# PCB_3U_Tester.net
KiCad netlist of a schematic drawn in Altium Designer
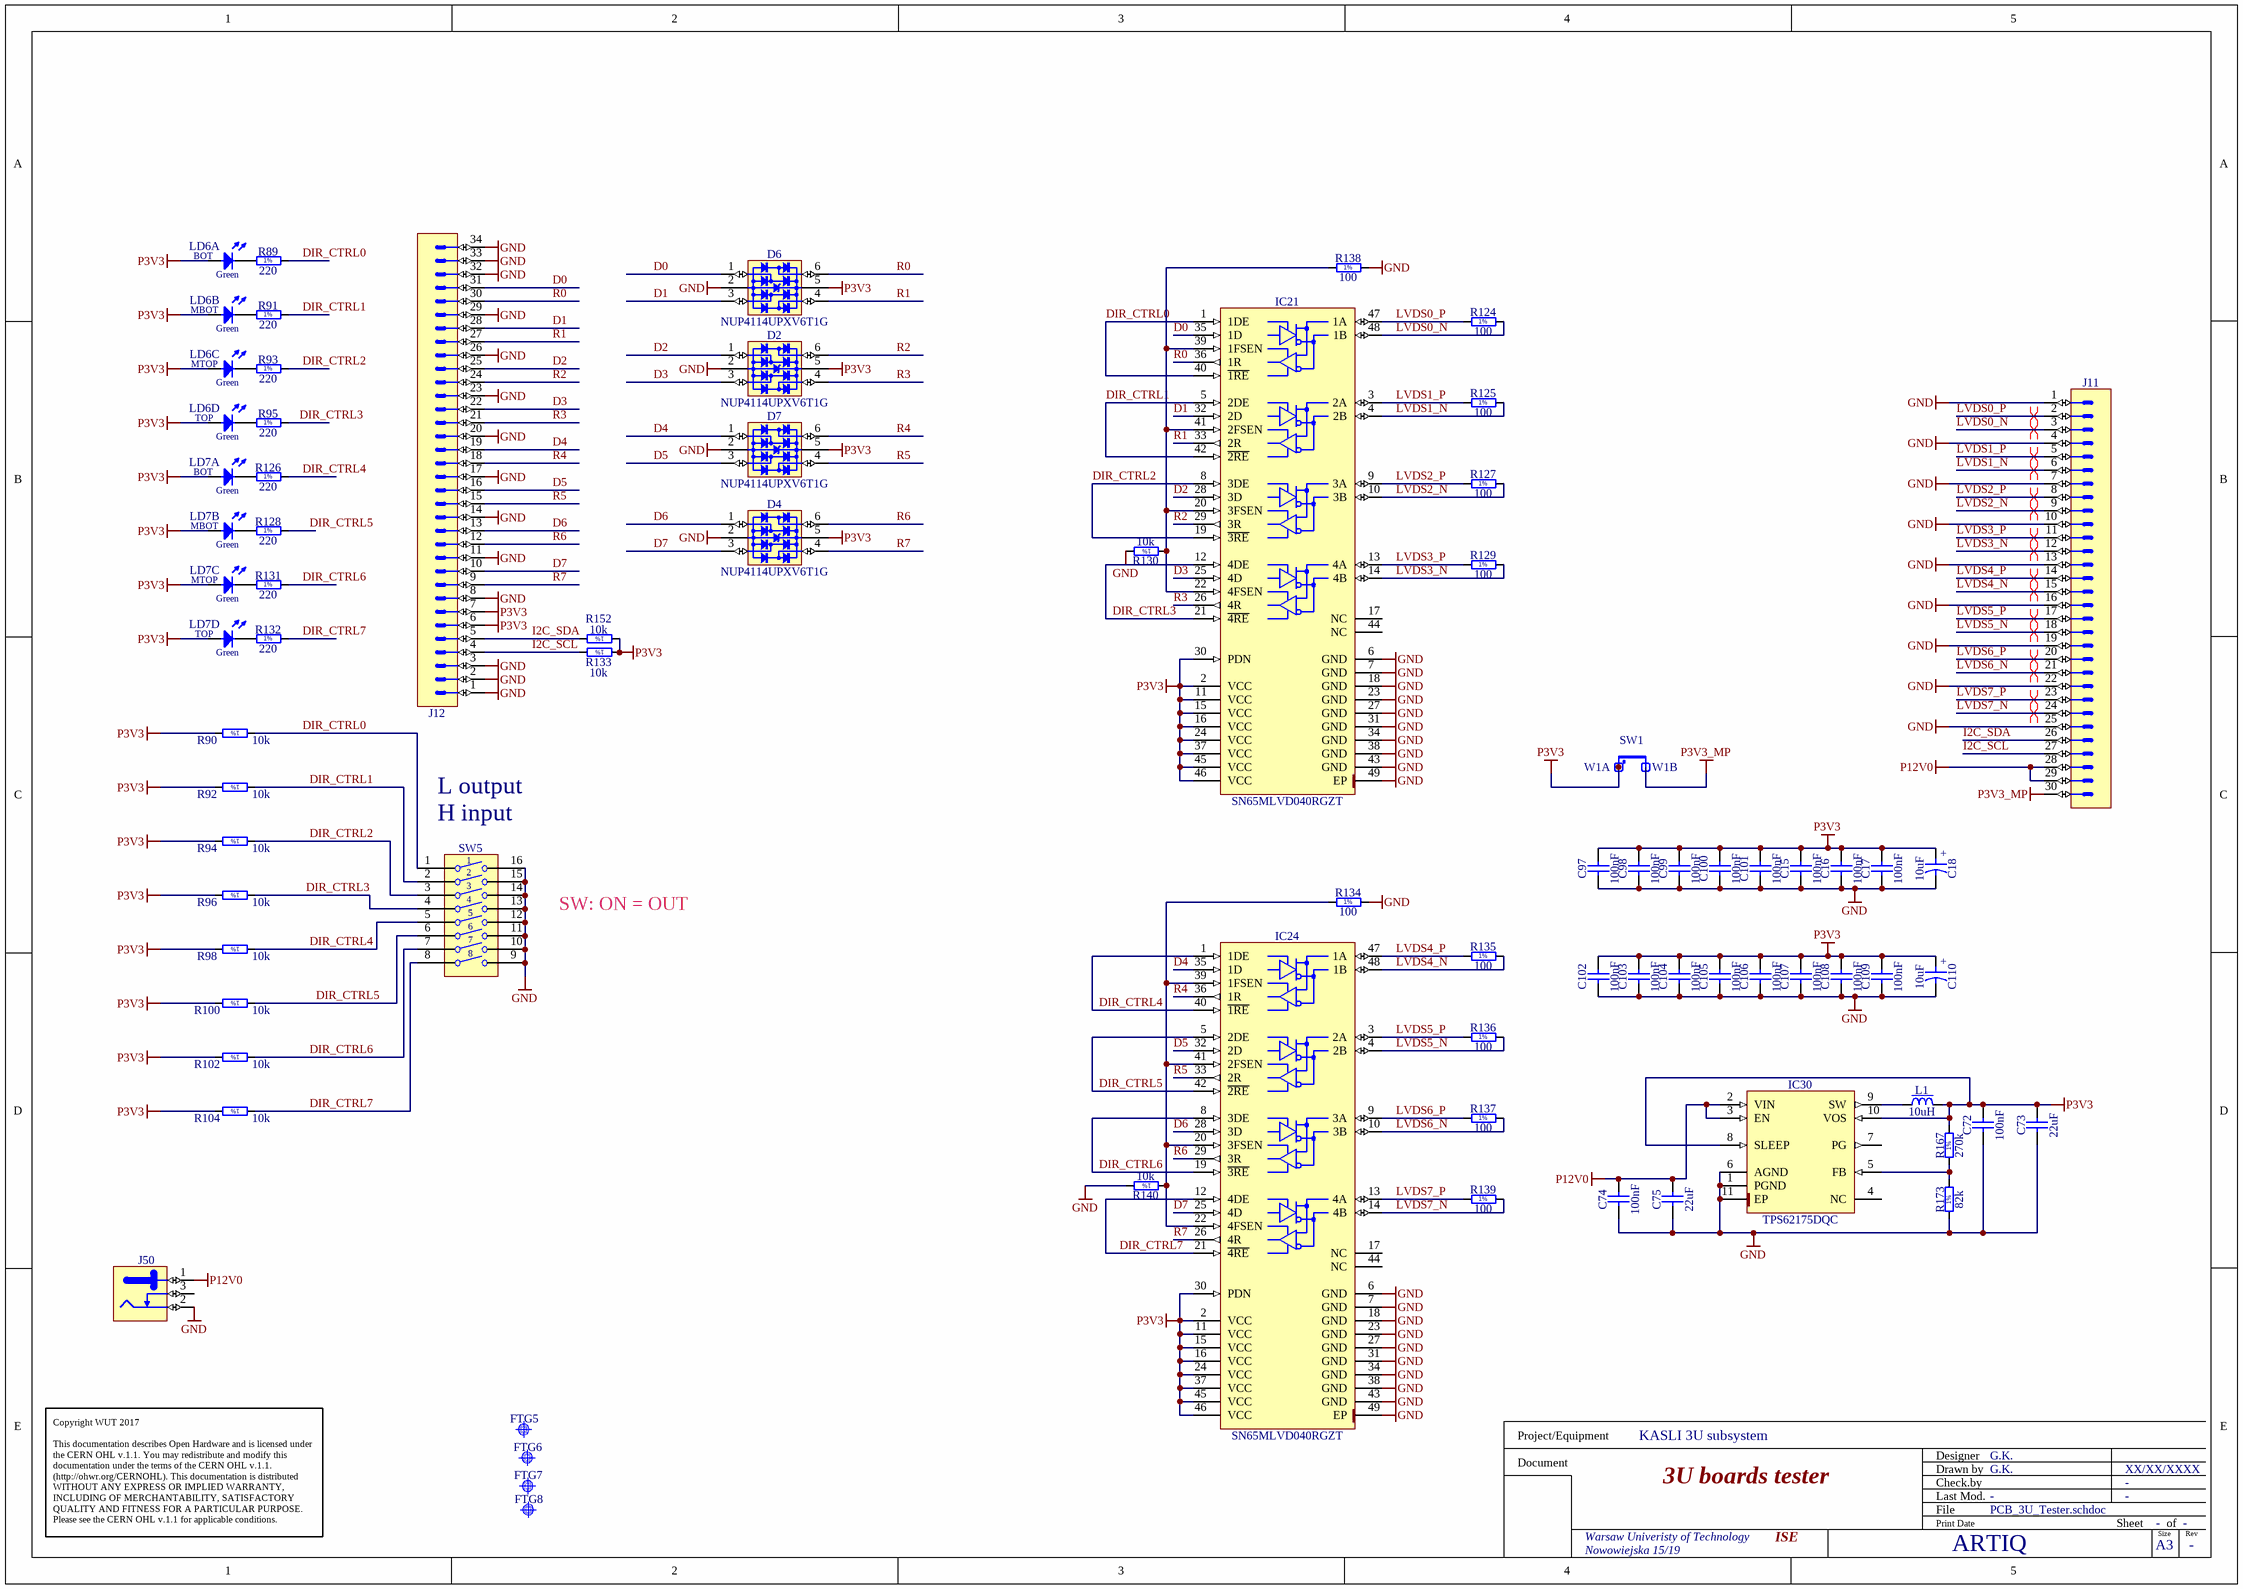
[diagram p0: PCB_3U_Tester.schdoc]

(export (version "E")
  (design (tool "Eeschema 10.0.6"))
  (components
    (comp (ref "C15")
      (value "100nF")
      (footprint "CAPC1005X55N")
      (description "Non-polarised capacitor")
      (fields (field (name "PART NUMBER") "CC0402_100NF_16V_10%_X5R") (field (name "VOLTAGE") "16V"))
      (libsource (lib "Capacitors") (part "Capacitor - non polarized"))
    )
    (comp (ref "C16")
      (value "100nF")
      (footprint "CAPC1005X55N")
      (description "Non-polarised capacitor")
      (fields (field (name "PART NUMBER") "CC0402_100NF_16V_10%_X5R") (field (name "VOLTAGE") "16V"))
      (libsource (lib "Capacitors") (part "Capacitor - non polarized"))
    )
    (comp (ref "C17")
      (value "100nF")
      (footprint "CAPC1005X55N")
      (description "Non-polarised capacitor")
      (fields (field (name "PART NUMBER") "CC0402_100NF_16V_10%_X5R") (field (name "VOLTAGE") "16V"))
      (libsource (lib "Capacitors") (part "Capacitor - non polarized"))
    )
    (comp (ref "C18")
      (value "10uF")
      (footprint "CAPAE430X540N")
      (description "Polarised capacitor")
      (fields (field (name "PART NUMBER") "CAE430-540_10UF_16V_20%") (field (name "VOLTAGE") "16V"))
      (libsource (lib "Capacitors") (part "Capacitor - polarized"))
    )
    (comp (ref "C72")
      (value "100nF")
      (footprint "CAPC1005X55N")
      (description "Non-polarised capacitor")
      (fields (field (name "PART NUMBER") "CC0402_100NF_16V_10%_X5R") (field (name "VOLTAGE") "16V"))
      (libsource (lib "Capacitors") (part "Capacitor - non polarized"))
    )
    (comp (ref "C73")
      (value "22uF")
      (footprint "CAPC2012X135N")
      (description "Non-polarised capacitor")
      (fields (field (name "PART NUMBER") "CC0805_22UF_16V_10%_X5R") (field (name "VOLTAGE") "16V"))
      (libsource (lib "Capacitors") (part "Capacitor - non polarized"))
    )
    (comp (ref "C74")
      (value "100nF")
      (footprint "CAPC1005X55N")
      (description "Non-polarised capacitor")
      (fields (field (name "PART NUMBER") "CC0402_100NF_16V_10%_X5R") (field (name "VOLTAGE") "16V"))
      (libsource (lib "Capacitors") (part "Capacitor - non polarized"))
    )
    (comp (ref "C75")
      (value "22uF")
      (footprint "CAPC2012X135N")
      (description "Non-polarised capacitor")
      (fields (field (name "PART NUMBER") "CC0805_22UF_16V_10%_X5R") (field (name "VOLTAGE") "16V"))
      (libsource (lib "Capacitors") (part "Capacitor - non polarized"))
    )
    (comp (ref "C97")
      (value "100nF")
      (footprint "CAPC1005X55N")
      (description "Non-polarised capacitor")
      (fields (field (name "PART NUMBER") "CC0402_100NF_16V_10%_X5R") (field (name "VOLTAGE") "16V"))
      (libsource (lib "Capacitors") (part "Capacitor - non polarized"))
    )
    (comp (ref "C98")
      (value "100nF")
      (footprint "CAPC1005X55N")
      (description "Non-polarised capacitor")
      (fields (field (name "PART NUMBER") "CC0402_100NF_16V_10%_X5R") (field (name "VOLTAGE") "16V"))
      (libsource (lib "Capacitors") (part "Capacitor - non polarized"))
    )
    (comp (ref "C99")
      (value "100nF")
      (footprint "CAPC1005X55N")
      (description "Non-polarised capacitor")
      (fields (field (name "PART NUMBER") "CC0402_100NF_16V_10%_X5R") (field (name "VOLTAGE") "16V"))
      (libsource (lib "Capacitors") (part "Capacitor - non polarized"))
    )
    (comp (ref "C100")
      (value "100nF")
      (footprint "CAPC1005X55N")
      (description "Non-polarised capacitor")
      (fields (field (name "PART NUMBER") "CC0402_100NF_16V_10%_X5R") (field (name "VOLTAGE") "16V"))
      (libsource (lib "Capacitors") (part "Capacitor - non polarized"))
    )
    (comp (ref "C101")
      (value "100nF")
      (footprint "CAPC1005X55N")
      (description "Non-polarised capacitor")
      (fields (field (name "PART NUMBER") "CC0402_100NF_16V_10%_X5R") (field (name "VOLTAGE") "16V"))
      (libsource (lib "Capacitors") (part "Capacitor - non polarized"))
    )
    (comp (ref "C102")
      (value "100nF")
      (footprint "CAPC1005X55N")
      (description "Non-polarised capacitor")
      (fields (field (name "PART NUMBER") "CC0402_100NF_16V_10%_X5R") (field (name "VOLTAGE") "16V"))
      (libsource (lib "Capacitors") (part "Capacitor - non polarized"))
    )
    (comp (ref "C103")
      (value "100nF")
      (footprint "CAPC1005X55N")
      (description "Non-polarised capacitor")
      (fields (field (name "PART NUMBER") "CC0402_100NF_16V_10%_X5R") (field (name "VOLTAGE") "16V"))
      (libsource (lib "Capacitors") (part "Capacitor - non polarized"))
    )
    (comp (ref "C104")
      (value "100nF")
      (footprint "CAPC1005X55N")
      (description "Non-polarised capacitor")
      (fields (field (name "PART NUMBER") "CC0402_100NF_16V_10%_X5R") (field (name "VOLTAGE") "16V"))
      (libsource (lib "Capacitors") (part "Capacitor - non polarized"))
    )
    (comp (ref "C105")
      (value "100nF")
      (footprint "CAPC1005X55N")
      (description "Non-polarised capacitor")
      (fields (field (name "PART NUMBER") "CC0402_100NF_16V_10%_X5R") (field (name "VOLTAGE") "16V"))
      (libsource (lib "Capacitors") (part "Capacitor - non polarized"))
    )
    (comp (ref "C106")
      (value "100nF")
      (footprint "CAPC1005X55N")
      (description "Non-polarised capacitor")
      (fields (field (name "PART NUMBER") "CC0402_100NF_16V_10%_X5R") (field (name "VOLTAGE") "16V"))
      (libsource (lib "Capacitors") (part "Capacitor - non polarized"))
    )
    (comp (ref "C107")
      (value "100nF")
      (footprint "CAPC1005X55N")
      (description "Non-polarised capacitor")
      (fields (field (name "PART NUMBER") "CC0402_100NF_16V_10%_X5R") (field (name "VOLTAGE") "16V"))
      (libsource (lib "Capacitors") (part "Capacitor - non polarized"))
    )
    (comp (ref "C108")
      (value "100nF")
      (footprint "CAPC1005X55N")
      (description "Non-polarised capacitor")
      (fields (field (name "PART NUMBER") "CC0402_100NF_16V_10%_X5R") (field (name "VOLTAGE") "16V"))
      (libsource (lib "Capacitors") (part "Capacitor - non polarized"))
    )
    (comp (ref "C109")
      (value "100nF")
      (footprint "CAPC1005X55N")
      (description "Non-polarised capacitor")
      (fields (field (name "PART NUMBER") "CC0402_100NF_16V_10%_X5R") (field (name "VOLTAGE") "16V"))
      (libsource (lib "Capacitors") (part "Capacitor - non polarized"))
    )
    (comp (ref "C110")
      (value "10uF")
      (footprint "CAPAE430X540N")
      (description "Polarised capacitor")
      (fields (field (name "PART NUMBER") "CAE430-540_10UF_16V_20%") (field (name "VOLTAGE") "16V"))
      (libsource (lib "Capacitors") (part "Capacitor - polarized"))
    )
    (comp (ref "D2")
      (value "NUP4114UPXV6T1G")
      (footprint "SOTFL50P160X60-6N")
      (fields (field (name "VOLTAGE") "5.5V") (field (name "MANUFACTURER") "ON SEMICONDUCTOR"))
      (libsource (lib "ICs And Semiconductors") (part "NUP4114"))
    )
    (comp (ref "D4")
      (value "NUP4114UPXV6T1G")
      (footprint "SOTFL50P160X60-6N")
      (fields (field (name "VOLTAGE") "5.5V") (field (name "MANUFACTURER") "ON SEMICONDUCTOR"))
      (libsource (lib "ICs And Semiconductors") (part "NUP4114"))
    )
    (comp (ref "D6")
      (value "NUP4114UPXV6T1G")
      (footprint "SOTFL50P160X60-6N")
      (fields (field (name "VOLTAGE") "5.5V") (field (name "MANUFACTURER") "ON SEMICONDUCTOR"))
      (libsource (lib "ICs And Semiconductors") (part "NUP4114"))
    )
    (comp (ref "D7")
      (value "NUP4114UPXV6T1G")
      (footprint "SOTFL50P160X60-6N")
      (fields (field (name "VOLTAGE") "5.5V") (field (name "MANUFACTURER") "ON SEMICONDUCTOR"))
      (libsource (lib "ICs And Semiconductors") (part "NUP4114"))
    )
    (comp (ref "FTG5")
      (value "Use only in PCB")
      (footprint "FIDUCIAL_TOP_C100-200")
      (description "Fiducial Target")
      (fields (field (name "PART NUMBER") "FIDUCIAL_TARGET_C100-200"))
      (libsource (lib "Eletro-mechanical") (part "Fiducial Target"))
    )
    (comp (ref "FTG6")
      (value "Use only in PCB")
      (footprint "FIDUCIAL_TOP_S100-200")
      (description "Fiducial Target")
      (fields (field (name "PART NUMBER") "FIDUCIAL_TARGET_S100-200"))
      (libsource (lib "Eletro-mechanical") (part "Fiducial Target"))
    )
    (comp (ref "FTG7")
      (value "Use only in PCB")
      (footprint "FIDUCIAL_TOP_S200-400")
      (description "Fiducial Target")
      (fields (field (name "PART NUMBER") "FIDUCIAL_TARGET_S200-400"))
      (libsource (lib "Eletro-mechanical") (part "Fiducial Target"))
    )
    (comp (ref "FTG8")
      (value "Use only in PCB")
      (footprint "FIDUCIAL_TOP_S100-200")
      (description "Fiducial Target")
      (fields (field (name "PART NUMBER") "FIDUCIAL_TARGET_S100-200"))
      (libsource (lib "Eletro-mechanical") (part "Fiducial Target"))
    )
    (comp (ref "IC21")
      (value "SN65MLVD040RGZT")
      (footprint "QFN50P700X700X100-49N-S420")
      (description "4-Channel Half-Duplex M-LVDS Line Transceiver")
      (fields (field (name "MANUFACTURER") "TEXAS INSTRUMENTS"))
      (libsource (lib "ICs And Semiconductors") (part "SN65MLVD040"))
    )
    (comp (ref "IC24")
      (value "SN65MLVD040RGZT")
      (footprint "QFN50P700X700X100-49N-S420")
      (description "4-Channel Half-Duplex M-LVDS Line Transceiver")
      (fields (field (name "MANUFACTURER") "TEXAS INSTRUMENTS"))
      (libsource (lib "ICs And Semiconductors") (part "SN65MLVD040"))
    )
    (comp (ref "IC30")
      (value "TPS62175DQC")
      (footprint "SON50P200X300X80-11N-R94X250")
      (description "4.75-28VDC to 1-6VDC, 500mA Step-Down Converter With Sleep Mode")
      (fields (field (name "MANUFACTURER") "TEXAS INSTRUMENTS"))
      (libsource (lib "ICs And Semiconductors") (part "TPS62175"))
    )
    (comp (ref "J11")
      (value "~")
      (footprint "3M_N2530-6002RB")
      (description "Connector 30 Male")
      (fields (field (name "PART NUMBER") "3M_N2530-6002RB") (field (name "MANUFACTURER") "3M"))
      (libsource (lib "Connectors") (part "Connector 30 Male"))
    )
    (comp (ref "J12")
      (value "Header 34")
      (footprint "3M_N2534-5002RB")
      (description "Connector 34 Male")
      (fields (field (name "PART NUMBER") "3M_N2534-5002RB") (field (name "MANUFACTURER") "3M"))
      (libsource (lib "Connectors") (part "Connector 34 Male"))
    )
    (comp (ref "J50")
      (value "Jack")
      (footprint "CUI_PJ-102BH")
      (description "2.5 mm Center Pin, 5A, 24V Right Angle, Through Hole, Tapered Pins, DC Power Jack Connector")
      (fields (field (name "PART NUMBER") "CUI_PJ-102BH") (field (name "MANUFACTURER") "CUI INC."))
      (libsource (lib "Connectors") (part "CUI_PJ-102BH"))
    )
    (comp (ref "L1")
      (value "10uH")
      (footprint "IND_MURATA-PS_8400")
      (description "Inductor With Core")
      (fields (field (name "PART NUMBER") "IND_10UH_10%_MURATA-PS_8400") (field (name "POWER") "950mA"))
      (libsource (lib "Inductors & Transformers") (part "Inductor With Magnetic core"))
    )
    (comp (ref "LD6")
      (value "Green")
      (footprint "LED_BIVAR_H485CGDL")
      (description "LED x4 Green 1C2A-BOT_3C4A_5C6A_7C8A-TOP")
      (fields (field (name "PART NUMBER") "LED_BIVAR_H485CGDL") (field (name "MANUFACTURER") "BIVAR"))
      (libsource (lib "ICs And Semiconductors") (part "LED x4 Green 1C2A-BOT_3C4A_5C6A_7C8A-TOP"))
    )
    (comp (ref "LD7")
      (value "Green")
      (footprint "LED_BIVAR_H485CGDL")
      (description "LED x4 Green 1C2A-BOT_3C4A_5C6A_7C8A-TOP")
      (fields (field (name "PART NUMBER") "LED_BIVAR_H485CGDL") (field (name "MANUFACTURER") "BIVAR"))
      (libsource (lib "ICs And Semiconductors") (part "LED x4 Green 1C2A-BOT_3C4A_5C6A_7C8A-TOP"))
    )
    (comp (ref "R89")
      (value "220")
      (footprint "RESC1608X55N")
      (description "Resistor - 1%")
      (fields (field (name "PART NUMBER") "R0603_220R_1%_0.1W_100PPM") (field (name "POWER") "0.1W"))
      (libsource (lib "Resistors") (part "Resistor - 1%"))
    )
    (comp (ref "R90")
      (value "10k")
      (footprint "RESC1005X40N")
      (description "Resistor - 1%")
      (fields (field (name "PART NUMBER") "R0402_10K_1%_0.0625W_100PPM") (field (name "POWER") "0.0625W"))
      (libsource (lib "Resistors") (part "Resistor - 1%"))
    )
    (comp (ref "R91")
      (value "220")
      (footprint "RESC1608X55N")
      (description "Resistor - 1%")
      (fields (field (name "PART NUMBER") "R0603_220R_1%_0.1W_100PPM") (field (name "POWER") "0.1W"))
      (libsource (lib "Resistors") (part "Resistor - 1%"))
    )
    (comp (ref "R92")
      (value "10k")
      (footprint "RESC1005X40N")
      (description "Resistor - 1%")
      (fields (field (name "PART NUMBER") "R0402_10K_1%_0.0625W_100PPM") (field (name "POWER") "0.0625W"))
      (libsource (lib "Resistors") (part "Resistor - 1%"))
    )
    (comp (ref "R93")
      (value "220")
      (footprint "RESC1608X55N")
      (description "Resistor - 1%")
      (fields (field (name "PART NUMBER") "R0603_220R_1%_0.1W_100PPM") (field (name "POWER") "0.1W"))
      (libsource (lib "Resistors") (part "Resistor - 1%"))
    )
    (comp (ref "R94")
      (value "10k")
      (footprint "RESC1005X40N")
      (description "Resistor - 1%")
      (fields (field (name "PART NUMBER") "R0402_10K_1%_0.0625W_100PPM") (field (name "POWER") "0.0625W"))
      (libsource (lib "Resistors") (part "Resistor - 1%"))
    )
    (comp (ref "R95")
      (value "220")
      (footprint "RESC1608X55N")
      (description "Resistor - 1%")
      (fields (field (name "PART NUMBER") "R0603_220R_1%_0.1W_100PPM") (field (name "POWER") "0.1W"))
      (libsource (lib "Resistors") (part "Resistor - 1%"))
    )
    (comp (ref "R96")
      (value "10k")
      (footprint "RESC1005X40N")
      (description "Resistor - 1%")
      (fields (field (name "PART NUMBER") "R0402_10K_1%_0.0625W_100PPM") (field (name "POWER") "0.0625W"))
      (libsource (lib "Resistors") (part "Resistor - 1%"))
    )
    (comp (ref "R98")
      (value "10k")
      (footprint "RESC1005X40N")
      (description "Resistor - 1%")
      (fields (field (name "PART NUMBER") "R0402_10K_1%_0.0625W_100PPM") (field (name "POWER") "0.0625W"))
      (libsource (lib "Resistors") (part "Resistor - 1%"))
    )
    (comp (ref "R100")
      (value "10k")
      (footprint "RESC1005X40N")
      (description "Resistor - 1%")
      (fields (field (name "PART NUMBER") "R0402_10K_1%_0.0625W_100PPM") (field (name "POWER") "0.0625W"))
      (libsource (lib "Resistors") (part "Resistor - 1%"))
    )
    (comp (ref "R102")
      (value "10k")
      (footprint "RESC1005X40N")
      (description "Resistor - 1%")
      (fields (field (name "PART NUMBER") "R0402_10K_1%_0.0625W_100PPM") (field (name "POWER") "0.0625W"))
      (libsource (lib "Resistors") (part "Resistor - 1%"))
    )
    (comp (ref "R104")
      (value "10k")
      (footprint "RESC1005X40N")
      (description "Resistor - 1%")
      (fields (field (name "PART NUMBER") "R0402_10K_1%_0.0625W_100PPM") (field (name "POWER") "0.0625W"))
      (libsource (lib "Resistors") (part "Resistor - 1%"))
    )
    (comp (ref "R124")
      (value "100")
      (footprint "RESC1005X40N")
      (description "Resistor - 1%")
      (fields (field (name "PART NUMBER") "R0402_100R_1%_0.1W_100PPM") (field (name "POWER") "0.1W"))
      (libsource (lib "Resistors") (part "Resistor - 1%"))
    )
    (comp (ref "R125")
      (value "100")
      (footprint "RESC1005X40N")
      (description "Resistor - 1%")
      (fields (field (name "PART NUMBER") "R0402_100R_1%_0.1W_100PPM") (field (name "POWER") "0.1W"))
      (libsource (lib "Resistors") (part "Resistor - 1%"))
    )
    (comp (ref "R126")
      (value "220")
      (footprint "RESC1608X55N")
      (description "Resistor - 1%")
      (fields (field (name "PART NUMBER") "R0603_220R_1%_0.1W_100PPM") (field (name "POWER") "0.1W"))
      (libsource (lib "Resistors") (part "Resistor - 1%"))
    )
    (comp (ref "R127")
      (value "100")
      (footprint "RESC1005X40N")
      (description "Resistor - 1%")
      (fields (field (name "PART NUMBER") "R0402_100R_1%_0.1W_100PPM") (field (name "POWER") "0.1W"))
      (libsource (lib "Resistors") (part "Resistor - 1%"))
    )
    (comp (ref "R128")
      (value "220")
      (footprint "RESC1608X55N")
      (description "Resistor - 1%")
      (fields (field (name "PART NUMBER") "R0603_220R_1%_0.1W_100PPM") (field (name "POWER") "0.1W"))
      (libsource (lib "Resistors") (part "Resistor - 1%"))
    )
    (comp (ref "R129")
      (value "100")
      (footprint "RESC1005X40N")
      (description "Resistor - 1%")
      (fields (field (name "PART NUMBER") "R0402_100R_1%_0.1W_100PPM") (field (name "POWER") "0.1W"))
      (libsource (lib "Resistors") (part "Resistor - 1%"))
    )
    (comp (ref "R130")
      (value "10k")
      (footprint "RESC1005X40N")
      (description "Resistor - 1%")
      (fields (field (name "PART NUMBER") "R0402_10K_1%_0.0625W_100PPM") (field (name "POWER") "0.0625W"))
      (libsource (lib "Resistors") (part "Resistor - 1%"))
    )
    (comp (ref "R131")
      (value "220")
      (footprint "RESC1608X55N")
      (description "Resistor - 1%")
      (fields (field (name "PART NUMBER") "R0603_220R_1%_0.1W_100PPM") (field (name "POWER") "0.1W"))
      (libsource (lib "Resistors") (part "Resistor - 1%"))
    )
    (comp (ref "R132")
      (value "220")
      (footprint "RESC1608X55N")
      (description "Resistor - 1%")
      (fields (field (name "PART NUMBER") "R0603_220R_1%_0.1W_100PPM") (field (name "POWER") "0.1W"))
      (libsource (lib "Resistors") (part "Resistor - 1%"))
    )
    (comp (ref "R133")
      (value "10k")
      (footprint "RESC1005X40N")
      (description "Resistor - 1%")
      (fields (field (name "PART NUMBER") "R0402_10K_1%_0.0625W_100PPM") (field (name "POWER") "0.0625W"))
      (libsource (lib "Resistors") (part "Resistor - 1%"))
    )
    (comp (ref "R134")
      (value "100")
      (footprint "RESC1005X40N")
      (description "Resistor - 1%")
      (fields (field (name "PART NUMBER") "R0402_100R_1%_0.1W_100PPM") (field (name "POWER") "0.1W"))
      (libsource (lib "Resistors") (part "Resistor - 1%"))
    )
    (comp (ref "R135")
      (value "100")
      (footprint "RESC1005X40N")
      (description "Resistor - 1%")
      (fields (field (name "PART NUMBER") "R0402_100R_1%_0.1W_100PPM") (field (name "POWER") "0.1W"))
      (libsource (lib "Resistors") (part "Resistor - 1%"))
    )
    (comp (ref "R136")
      (value "100")
      (footprint "RESC1005X40N")
      (description "Resistor - 1%")
      (fields (field (name "PART NUMBER") "R0402_100R_1%_0.1W_100PPM") (field (name "POWER") "0.1W"))
      (libsource (lib "Resistors") (part "Resistor - 1%"))
    )
    (comp (ref "R137")
      (value "100")
      (footprint "RESC1005X40N")
      (description "Resistor - 1%")
      (fields (field (name "PART NUMBER") "R0402_100R_1%_0.1W_100PPM") (field (name "POWER") "0.1W"))
      (libsource (lib "Resistors") (part "Resistor - 1%"))
    )
    (comp (ref "R138")
      (value "100")
      (footprint "RESC1005X40N")
      (description "Resistor - 1%")
      (fields (field (name "PART NUMBER") "R0402_100R_1%_0.1W_100PPM") (field (name "POWER") "0.1W"))
      (libsource (lib "Resistors") (part "Resistor - 1%"))
    )
    (comp (ref "R139")
      (value "100")
      (footprint "RESC1005X40N")
      (description "Resistor - 1%")
      (fields (field (name "PART NUMBER") "R0402_100R_1%_0.1W_100PPM") (field (name "POWER") "0.1W"))
      (libsource (lib "Resistors") (part "Resistor - 1%"))
    )
    (comp (ref "R140")
      (value "10k")
      (footprint "RESC1005X40N")
      (description "Resistor - 1%")
      (fields (field (name "PART NUMBER") "R0402_10K_1%_0.0625W_100PPM") (field (name "POWER") "0.0625W"))
      (libsource (lib "Resistors") (part "Resistor - 1%"))
    )
    (comp (ref "R152")
      (value "10k")
      (footprint "RESC1005X40N")
      (description "Resistor - 1%")
      (fields (field (name "PART NUMBER") "R0402_10K_1%_0.0625W_100PPM") (field (name "POWER") "0.0625W"))
      (libsource (lib "Resistors") (part "Resistor - 1%"))
    )
    (comp (ref "R167")
      (value "270k")
      (footprint "RESC1608X55N")
      (description "Resistor - 1%")
      (fields (field (name "PART NUMBER") "R0603_270K_1%_0.1W_100PPM") (field (name "POWER") "0.1W"))
      (libsource (lib "Resistors") (part "Resistor - 1%"))
    )
    (comp (ref "R173")
      (value "82k")
      (footprint "RESC1608X55N")
      (description "Resistor - 1%")
      (fields (field (name "PART NUMBER") "R0603_82K_1%_0.1W_100PPM") (field (name "POWER") "0.1W"))
      (libsource (lib "Resistors") (part "Resistor - 1%"))
    )
    (comp (ref "SW1")
      (value "Jumper Type1")
      (footprint "JUMPER_BLACK_INSULATED_2.54MM")
      (description "Jumper 1 Pin")
      (fields
        (field (name "PART NUMBER") "COMATEL_313.1730.0.00.40.0")
        (field (name "MANUFACTURER") "KONTEK COMATEL")
      )
      (libsource (lib "Connectors") (part "Jumper Type1"))
    )
    (comp (ref "SW5")
      (value "Switch")
      (footprint "SW_TYCO_1-1571983-0")
      (description "8 Ways SPST DIP Switch")
      (fields (field (name "PART NUMBER") "SW_TYCO_1-1571983-0") (field (name "MANUFACTURER") "TYCO"))
      (libsource (lib "Eletro-mechanical") (part "SW 8x SPST DIP Switch"))
    )
    (comp (ref "W1")
      (value "Test Point")
      (footprint "COMATEL_385.0358.1.02.400")
      (description "2 Mini Wire-Wrap Contact Strip Header")
      (fields
        (field (name "PART NUMBER") "COMATEL_385.0358.1.02.400")
        (field (name "MANUFACTURER") "KONTEK COMATEL")
      )
      (libsource (lib "Connectors") (part "Wire-Wrap Contact x2"))
    )
  )
  (nets
    (net (code "1") (name "/D0") (class "Default")
      (node (ref "D6") (pin "1") (pinfunction "I/O1_1") (pintype "bidirectional"))
      (node (ref "IC21") (pin "35") (pinfunction "1D_35") (pintype "input"))
      (node (ref "J12") (pin "31") (pinfunction "31_31") (pintype "bidirectional"))
    )
    (net (code "2") (name "/D1") (class "Default")
      (node (ref "D6") (pin "3") (pinfunction "I/O2_3") (pintype "bidirectional"))
      (node (ref "IC21") (pin "32") (pinfunction "2D_32") (pintype "input"))
      (node (ref "J12") (pin "28") (pinfunction "28_28") (pintype "bidirectional"))
    )
    (net (code "3") (name "/D2") (class "Default")
      (node (ref "D2") (pin "1") (pinfunction "I/O1_1") (pintype "bidirectional"))
      (node (ref "IC21") (pin "28") (pinfunction "3D_28") (pintype "input"))
      (node (ref "J12") (pin "25") (pinfunction "25_25") (pintype "bidirectional"))
    )
    (net (code "4") (name "/D3") (class "Default")
      (node (ref "D2") (pin "3") (pinfunction "I/O2_3") (pintype "bidirectional"))
      (node (ref "IC21") (pin "25") (pinfunction "4D_25") (pintype "input"))
      (node (ref "J12") (pin "22") (pinfunction "22_22") (pintype "bidirectional"))
    )
    (net (code "5") (name "/D4") (class "Default")
      (node (ref "D7") (pin "1") (pinfunction "I/O1_1") (pintype "bidirectional"))
      (node (ref "IC24") (pin "35") (pinfunction "1D_35") (pintype "input"))
      (node (ref "J12") (pin "19") (pinfunction "19_19") (pintype "bidirectional"))
    )
    (net (code "6") (name "/D5") (class "Default")
      (node (ref "D7") (pin "3") (pinfunction "I/O2_3") (pintype "bidirectional"))
      (node (ref "IC24") (pin "32") (pinfunction "2D_32") (pintype "input"))
      (node (ref "J12") (pin "16") (pinfunction "16_16") (pintype "bidirectional"))
    )
    (net (code "7") (name "/D6") (class "Default")
      (node (ref "D4") (pin "1") (pinfunction "I/O1_1") (pintype "bidirectional"))
      (node (ref "IC24") (pin "28") (pinfunction "3D_28") (pintype "input"))
      (node (ref "J12") (pin "13") (pinfunction "13_13") (pintype "bidirectional"))
    )
    (net (code "8") (name "/D7") (class "Default")
      (node (ref "D4") (pin "3") (pinfunction "I/O2_3") (pintype "bidirectional"))
      (node (ref "IC24") (pin "25") (pinfunction "4D_25") (pintype "input"))
      (node (ref "J12") (pin "10") (pinfunction "10_10") (pintype "bidirectional"))
    )
    (net (code "9") (name "/DIR_CTRL0") (class "Default")
      (node (ref "IC21") (pin "1") (pinfunction "1DE_1") (pintype "input"))
      (node (ref "IC21") (pin "40") (pinfunction "~{1RE}_40") (pintype "input"))
      (node (ref "R89") (pin "2") (pinfunction "2_2") (pintype "passive"))
      (node (ref "R90") (pin "1") (pinfunction "1_1") (pintype "passive"))
      (node (ref "SW5") (pin "1") (pinfunction "1_1") (pintype "passive"))
    )
    (net (code "10") (name "/DIR_CTRL1") (class "Default")
      (node (ref "IC21") (pin "42") (pinfunction "~{2RE}_42") (pintype "input"))
      (node (ref "IC21") (pin "5") (pinfunction "2DE_5") (pintype "input"))
      (node (ref "R91") (pin "2") (pinfunction "2_2") (pintype "passive"))
      (node (ref "R92") (pin "1") (pinfunction "1_1") (pintype "passive"))
      (node (ref "SW5") (pin "2") (pinfunction "2_2") (pintype "passive"))
    )
    (net (code "11") (name "/DIR_CTRL2") (class "Default")
      (node (ref "IC21") (pin "19") (pinfunction "~{3RE}_19") (pintype "input"))
      (node (ref "IC21") (pin "8") (pinfunction "3DE_8") (pintype "input"))
      (node (ref "R93") (pin "2") (pinfunction "2_2") (pintype "passive"))
      (node (ref "R94") (pin "1") (pinfunction "1_1") (pintype "passive"))
      (node (ref "SW5") (pin "3") (pinfunction "3_3") (pintype "passive"))
    )
    (net (code "12") (name "/DIR_CTRL3") (class "Default")
      (node (ref "IC21") (pin "12") (pinfunction "4DE_12") (pintype "input"))
      (node (ref "IC21") (pin "21") (pinfunction "~{4RE}_21") (pintype "input"))
      (node (ref "R95") (pin "2") (pinfunction "2_2") (pintype "passive"))
      (node (ref "R96") (pin "1") (pinfunction "1_1") (pintype "passive"))
      (node (ref "SW5") (pin "4") (pinfunction "4_4") (pintype "passive"))
    )
    (net (code "13") (name "/DIR_CTRL4") (class "Default")
      (node (ref "IC24") (pin "1") (pinfunction "1DE_1") (pintype "input"))
      (node (ref "IC24") (pin "40") (pinfunction "~{1RE}_40") (pintype "input"))
      (node (ref "R126") (pin "2") (pinfunction "2_2") (pintype "passive"))
      (node (ref "R98") (pin "1") (pinfunction "1_1") (pintype "passive"))
      (node (ref "SW5") (pin "5") (pinfunction "5_5") (pintype "passive"))
    )
    (net (code "14") (name "/DIR_CTRL5") (class "Default")
      (node (ref "IC24") (pin "42") (pinfunction "~{2RE}_42") (pintype "input"))
      (node (ref "IC24") (pin "5") (pinfunction "2DE_5") (pintype "input"))
      (node (ref "R100") (pin "1") (pinfunction "1_1") (pintype "passive"))
      (node (ref "R128") (pin "2") (pinfunction "2_2") (pintype "passive"))
      (node (ref "SW5") (pin "6") (pinfunction "6_6") (pintype "passive"))
    )
    (net (code "15") (name "/DIR_CTRL6") (class "Default")
      (node (ref "IC24") (pin "19") (pinfunction "~{3RE}_19") (pintype "input"))
      (node (ref "IC24") (pin "8") (pinfunction "3DE_8") (pintype "input"))
      (node (ref "R102") (pin "1") (pinfunction "1_1") (pintype "passive"))
      (node (ref "R131") (pin "2") (pinfunction "2_2") (pintype "passive"))
      (node (ref "SW5") (pin "7") (pinfunction "7_7") (pintype "passive"))
    )
    (net (code "16") (name "/DIR_CTRL7") (class "Default")
      (node (ref "IC24") (pin "12") (pinfunction "4DE_12") (pintype "input"))
      (node (ref "IC24") (pin "21") (pinfunction "~{4RE}_21") (pintype "input"))
      (node (ref "R104") (pin "1") (pinfunction "1_1") (pintype "passive"))
      (node (ref "R132") (pin "2") (pinfunction "2_2") (pintype "passive"))
      (node (ref "SW5") (pin "8") (pinfunction "8_8") (pintype "passive"))
    )
    (net (code "17") (name "/I2C_SCL") (class "Default")
      (node (ref "J11") (pin "27") (pinfunction "27_27") (pintype "bidirectional"))
      (node (ref "J12") (pin "4") (pinfunction "4_4") (pintype "bidirectional"))
      (node (ref "R133") (pin "2") (pinfunction "2_2") (pintype "passive"))
    )
    (net (code "18") (name "/I2C_SDA") (class "Default")
      (node (ref "J11") (pin "26") (pinfunction "26_26") (pintype "bidirectional"))
      (node (ref "J12") (pin "5") (pinfunction "5_5") (pintype "bidirectional"))
      (node (ref "R152") (pin "2") (pinfunction "2_2") (pintype "passive"))
    )
    (net (code "19") (name "/LVDS0_N") (class "Default")
      (node (ref "IC21") (pin "48") (pinfunction "1B_48") (pintype "bidirectional"))
      (node (ref "J11") (pin "3") (pinfunction "3_3") (pintype "bidirectional"))
      (node (ref "R124") (pin "2") (pinfunction "2_2") (pintype "passive"))
    )
    (net (code "20") (name "/LVDS0_P") (class "Default")
      (node (ref "IC21") (pin "47") (pinfunction "1A_47") (pintype "bidirectional"))
      (node (ref "J11") (pin "2") (pinfunction "2_2") (pintype "bidirectional"))
      (node (ref "R124") (pin "1") (pinfunction "1_1") (pintype "passive"))
    )
    (net (code "21") (name "/LVDS1_N") (class "Default")
      (node (ref "IC21") (pin "4") (pinfunction "2B_4") (pintype "bidirectional"))
      (node (ref "J11") (pin "6") (pinfunction "6_6") (pintype "bidirectional"))
      (node (ref "R125") (pin "2") (pinfunction "2_2") (pintype "passive"))
    )
    (net (code "22") (name "/LVDS1_P") (class "Default")
      (node (ref "IC21") (pin "3") (pinfunction "2A_3") (pintype "bidirectional"))
      (node (ref "J11") (pin "5") (pinfunction "5_5") (pintype "bidirectional"))
      (node (ref "R125") (pin "1") (pinfunction "1_1") (pintype "passive"))
    )
    (net (code "23") (name "/LVDS2_N") (class "Default")
      (node (ref "IC21") (pin "10") (pinfunction "3B_10") (pintype "bidirectional"))
      (node (ref "J11") (pin "9") (pinfunction "9_9") (pintype "bidirectional"))
      (node (ref "R127") (pin "2") (pinfunction "2_2") (pintype "passive"))
    )
    (net (code "24") (name "/LVDS2_P") (class "Default")
      (node (ref "IC21") (pin "9") (pinfunction "3A_9") (pintype "bidirectional"))
      (node (ref "J11") (pin "8") (pinfunction "8_8") (pintype "bidirectional"))
      (node (ref "R127") (pin "1") (pinfunction "1_1") (pintype "passive"))
    )
    (net (code "25") (name "/LVDS3_N") (class "Default")
      (node (ref "IC21") (pin "14") (pinfunction "4B_14") (pintype "bidirectional"))
      (node (ref "J11") (pin "12") (pinfunction "12_12") (pintype "bidirectional"))
      (node (ref "R129") (pin "2") (pinfunction "2_2") (pintype "passive"))
    )
    (net (code "26") (name "/LVDS3_P") (class "Default")
      (node (ref "IC21") (pin "13") (pinfunction "4A_13") (pintype "bidirectional"))
      (node (ref "J11") (pin "11") (pinfunction "11_11") (pintype "bidirectional"))
      (node (ref "R129") (pin "1") (pinfunction "1_1") (pintype "passive"))
    )
    (net (code "27") (name "/LVDS4_N") (class "Default")
      (node (ref "IC24") (pin "48") (pinfunction "1B_48") (pintype "bidirectional"))
      (node (ref "J11") (pin "15") (pinfunction "15_15") (pintype "bidirectional"))
      (node (ref "R135") (pin "2") (pinfunction "2_2") (pintype "passive"))
    )
    (net (code "28") (name "/LVDS4_P") (class "Default")
      (node (ref "IC24") (pin "47") (pinfunction "1A_47") (pintype "bidirectional"))
      (node (ref "J11") (pin "14") (pinfunction "14_14") (pintype "bidirectional"))
      (node (ref "R135") (pin "1") (pinfunction "1_1") (pintype "passive"))
    )
    (net (code "29") (name "/LVDS5_N") (class "Default")
      (node (ref "IC24") (pin "4") (pinfunction "2B_4") (pintype "bidirectional"))
      (node (ref "J11") (pin "18") (pinfunction "18_18") (pintype "bidirectional"))
      (node (ref "R136") (pin "2") (pinfunction "2_2") (pintype "passive"))
    )
    (net (code "30") (name "/LVDS5_P") (class "Default")
      (node (ref "IC24") (pin "3") (pinfunction "2A_3") (pintype "bidirectional"))
      (node (ref "J11") (pin "17") (pinfunction "17_17") (pintype "bidirectional"))
      (node (ref "R136") (pin "1") (pinfunction "1_1") (pintype "passive"))
    )
    (net (code "31") (name "/LVDS6_N") (class "Default")
      (node (ref "IC24") (pin "10") (pinfunction "3B_10") (pintype "bidirectional"))
      (node (ref "J11") (pin "21") (pinfunction "21_21") (pintype "bidirectional"))
      (node (ref "R137") (pin "2") (pinfunction "2_2") (pintype "passive"))
    )
    (net (code "32") (name "/LVDS6_P") (class "Default")
      (node (ref "IC24") (pin "9") (pinfunction "3A_9") (pintype "bidirectional"))
      (node (ref "J11") (pin "20") (pinfunction "20_20") (pintype "bidirectional"))
      (node (ref "R137") (pin "1") (pinfunction "1_1") (pintype "passive"))
    )
    (net (code "33") (name "/LVDS7_N") (class "Default")
      (node (ref "IC24") (pin "14") (pinfunction "4B_14") (pintype "bidirectional"))
      (node (ref "J11") (pin "24") (pinfunction "24_24") (pintype "bidirectional"))
      (node (ref "R139") (pin "2") (pinfunction "2_2") (pintype "passive"))
    )
    (net (code "34") (name "/LVDS7_P") (class "Default")
      (node (ref "IC24") (pin "13") (pinfunction "4A_13") (pintype "bidirectional"))
      (node (ref "J11") (pin "23") (pinfunction "23_23") (pintype "bidirectional"))
      (node (ref "R139") (pin "1") (pinfunction "1_1") (pintype "passive"))
    )
    (net (code "35") (name "/R0") (class "Default")
      (node (ref "D6") (pin "6") (pinfunction "I/O4_6") (pintype "bidirectional"))
      (node (ref "IC21") (pin "36") (pinfunction "1R_36") (pintype "output"))
      (node (ref "J12") (pin "30") (pinfunction "30_30") (pintype "bidirectional"))
    )
    (net (code "36") (name "/R1") (class "Default")
      (node (ref "D6") (pin "4") (pinfunction "I/O3_4") (pintype "bidirectional"))
      (node (ref "IC21") (pin "33") (pinfunction "2R_33") (pintype "output"))
      (node (ref "J12") (pin "27") (pinfunction "27_27") (pintype "bidirectional"))
    )
    (net (code "37") (name "/R2") (class "Default")
      (node (ref "D2") (pin "6") (pinfunction "I/O4_6") (pintype "bidirectional"))
      (node (ref "IC21") (pin "29") (pinfunction "3R_29") (pintype "output"))
      (node (ref "J12") (pin "24") (pinfunction "24_24") (pintype "bidirectional"))
    )
    (net (code "38") (name "/R3") (class "Default")
      (node (ref "D2") (pin "4") (pinfunction "I/O3_4") (pintype "bidirectional"))
      (node (ref "IC21") (pin "26") (pinfunction "4R_26") (pintype "output"))
      (node (ref "J12") (pin "21") (pinfunction "21_21") (pintype "bidirectional"))
    )
    (net (code "39") (name "/R4") (class "Default")
      (node (ref "D7") (pin "6") (pinfunction "I/O4_6") (pintype "bidirectional"))
      (node (ref "IC24") (pin "36") (pinfunction "1R_36") (pintype "output"))
      (node (ref "J12") (pin "18") (pinfunction "18_18") (pintype "bidirectional"))
    )
    (net (code "40") (name "/R5") (class "Default")
      (node (ref "D7") (pin "4") (pinfunction "I/O3_4") (pintype "bidirectional"))
      (node (ref "IC24") (pin "33") (pinfunction "2R_33") (pintype "output"))
      (node (ref "J12") (pin "15") (pinfunction "15_15") (pintype "bidirectional"))
    )
    (net (code "41") (name "/R6") (class "Default")
      (node (ref "D4") (pin "6") (pinfunction "I/O4_6") (pintype "bidirectional"))
      (node (ref "IC24") (pin "29") (pinfunction "3R_29") (pintype "output"))
      (node (ref "J12") (pin "12") (pinfunction "12_12") (pintype "bidirectional"))
    )
    (net (code "42") (name "/R7") (class "Default")
      (node (ref "D4") (pin "4") (pinfunction "I/O3_4") (pintype "bidirectional"))
      (node (ref "IC24") (pin "26") (pinfunction "4R_26") (pintype "output"))
      (node (ref "J12") (pin "9") (pinfunction "9_9") (pintype "bidirectional"))
    )
    (net (code "43") (name "GND") (class "Default")
      (node (ref "C100") (pin "1") (pinfunction "1_1") (pintype "passive"))
      (node (ref "C101") (pin "1") (pinfunction "1_1") (pintype "passive"))
      (node (ref "C102") (pin "1") (pinfunction "1_1") (pintype "passive"))
      (node (ref "C103") (pin "1") (pinfunction "1_1") (pintype "passive"))
      (node (ref "C104") (pin "1") (pinfunction "1_1") (pintype "passive"))
      (node (ref "C105") (pin "1") (pinfunction "1_1") (pintype "passive"))
      (node (ref "C106") (pin "1") (pinfunction "1_1") (pintype "passive"))
      (node (ref "C107") (pin "1") (pinfunction "1_1") (pintype "passive"))
      (node (ref "C108") (pin "1") (pinfunction "1_1") (pintype "passive"))
      (node (ref "C109") (pin "1") (pinfunction "1_1") (pintype "passive"))
      (node (ref "C110") (pin "2") (pinfunction "2_2") (pintype "passive"))
      (node (ref "C15") (pin "1") (pinfunction "1_1") (pintype "passive"))
      (node (ref "C16") (pin "1") (pinfunction "1_1") (pintype "passive"))
      (node (ref "C17") (pin "1") (pinfunction "1_1") (pintype "passive"))
      (node (ref "C18") (pin "2") (pinfunction "2_2") (pintype "passive"))
      (node (ref "C72") (pin "1") (pinfunction "1_1") (pintype "passive"))
      (node (ref "C73") (pin "1") (pinfunction "1_1") (pintype "passive"))
      (node (ref "C74") (pin "1") (pinfunction "1_1") (pintype "passive"))
      (node (ref "C75") (pin "1") (pinfunction "1_1") (pintype "passive"))
      (node (ref "C97") (pin "1") (pinfunction "1_1") (pintype "passive"))
      (node (ref "C98") (pin "1") (pinfunction "1_1") (pintype "passive"))
      (node (ref "C99") (pin "1") (pinfunction "1_1") (pintype "passive"))
      (node (ref "D2") (pin "2") (pinfunction "GND_2") (pintype "power_in"))
      (node (ref "D4") (pin "2") (pinfunction "GND_2") (pintype "power_in"))
      (node (ref "D6") (pin "2") (pinfunction "GND_2") (pintype "power_in"))
      (node (ref "D7") (pin "2") (pinfunction "GND_2") (pintype "power_in"))
      (node (ref "IC21") (pin "18") (pinfunction "GND_18") (pintype "power_in"))
      (node (ref "IC21") (pin "23") (pinfunction "GND_23") (pintype "power_in"))
      (node (ref "IC21") (pin "27") (pinfunction "GND_27") (pintype "power_in"))
      (node (ref "IC21") (pin "31") (pinfunction "GND_31") (pintype "power_in"))
      (node (ref "IC21") (pin "34") (pinfunction "GND_34") (pintype "power_in"))
      (node (ref "IC21") (pin "38") (pinfunction "GND_38") (pintype "power_in"))
      (node (ref "IC21") (pin "43") (pinfunction "GND_43") (pintype "power_in"))
      (node (ref "IC21") (pin "49") (pinfunction "EP_49") (pintype "power_in"))
      (node (ref "IC21") (pin "6") (pinfunction "GND_6") (pintype "power_in"))
      (node (ref "IC21") (pin "7") (pinfunction "GND_7") (pintype "power_in"))
      (node (ref "IC24") (pin "18") (pinfunction "GND_18") (pintype "power_in"))
      (node (ref "IC24") (pin "23") (pinfunction "GND_23") (pintype "power_in"))
      (node (ref "IC24") (pin "27") (pinfunction "GND_27") (pintype "power_in"))
      (node (ref "IC24") (pin "31") (pinfunction "GND_31") (pintype "power_in"))
      (node (ref "IC24") (pin "34") (pinfunction "GND_34") (pintype "power_in"))
      (node (ref "IC24") (pin "38") (pinfunction "GND_38") (pintype "power_in"))
      (node (ref "IC24") (pin "43") (pinfunction "GND_43") (pintype "power_in"))
      (node (ref "IC24") (pin "49") (pinfunction "EP_49") (pintype "power_in"))
      (node (ref "IC24") (pin "6") (pinfunction "GND_6") (pintype "power_in"))
      (node (ref "IC24") (pin "7") (pinfunction "GND_7") (pintype "power_in"))
      (node (ref "IC30") (pin "1") (pinfunction "PGND_1") (pintype "power_in"))
      (node (ref "IC30") (pin "11") (pinfunction "EP_11") (pintype "power_in"))
      (node (ref "IC30") (pin "6") (pinfunction "AGND_6") (pintype "power_in"))
      (node (ref "J11") (pin "1") (pinfunction "1_1") (pintype "bidirectional"))
      (node (ref "J11") (pin "10") (pinfunction "10_10") (pintype "bidirectional"))
      (node (ref "J11") (pin "13") (pinfunction "13_13") (pintype "bidirectional"))
      (node (ref "J11") (pin "16") (pinfunction "16_16") (pintype "bidirectional"))
      (node (ref "J11") (pin "19") (pinfunction "19_19") (pintype "bidirectional"))
      (node (ref "J11") (pin "22") (pinfunction "22_22") (pintype "bidirectional"))
      (node (ref "J11") (pin "25") (pinfunction "25_25") (pintype "bidirectional"))
      (node (ref "J11") (pin "4") (pinfunction "4_4") (pintype "bidirectional"))
      (node (ref "J11") (pin "7") (pinfunction "7_7") (pintype "bidirectional"))
      (node (ref "J12") (pin "1") (pinfunction "1_1") (pintype "bidirectional"))
      (node (ref "J12") (pin "11") (pinfunction "11_11") (pintype "bidirectional"))
      (node (ref "J12") (pin "14") (pinfunction "14_14") (pintype "bidirectional"))
      (node (ref "J12") (pin "17") (pinfunction "17_17") (pintype "bidirectional"))
      (node (ref "J12") (pin "2") (pinfunction "2_2") (pintype "bidirectional"))
      (node (ref "J12") (pin "20") (pinfunction "20_20") (pintype "bidirectional"))
      (node (ref "J12") (pin "23") (pinfunction "23_23") (pintype "bidirectional"))
      (node (ref "J12") (pin "26") (pinfunction "26_26") (pintype "bidirectional"))
      (node (ref "J12") (pin "29") (pinfunction "29_29") (pintype "bidirectional"))
      (node (ref "J12") (pin "3") (pinfunction "3_3") (pintype "bidirectional"))
      (node (ref "J12") (pin "32") (pinfunction "32_32") (pintype "bidirectional"))
      (node (ref "J12") (pin "33") (pinfunction "33_33") (pintype "bidirectional"))
      (node (ref "J12") (pin "34") (pinfunction "34_34") (pintype "bidirectional"))
      (node (ref "J12") (pin "8") (pinfunction "8_8") (pintype "bidirectional"))
      (node (ref "J50") (pin "2") (pinfunction "2_2") (pintype "bidirectional"))
      (node (ref "R130") (pin "2") (pinfunction "2_2") (pintype "passive"))
      (node (ref "R134") (pin "2") (pinfunction "2_2") (pintype "passive"))
      (node (ref "R138") (pin "2") (pinfunction "2_2") (pintype "passive"))
      (node (ref "R140") (pin "2") (pinfunction "2_2") (pintype "passive"))
      (node (ref "R173") (pin "1") (pinfunction "1_1") (pintype "passive"))
      (node (ref "SW5") (pin "10") (pinfunction "10_10") (pintype "passive"))
      (node (ref "SW5") (pin "11") (pinfunction "11_11") (pintype "passive"))
      (node (ref "SW5") (pin "12") (pinfunction "12_12") (pintype "passive"))
      (node (ref "SW5") (pin "13") (pinfunction "13_13") (pintype "passive"))
      (node (ref "SW5") (pin "14") (pinfunction "14_14") (pintype "passive"))
      (node (ref "SW5") (pin "15") (pinfunction "15_15") (pintype "passive"))
      (node (ref "SW5") (pin "16") (pinfunction "16_16") (pintype "passive"))
      (node (ref "SW5") (pin "9") (pinfunction "9_9") (pintype "passive"))
    )
    (net (code "44") (name "Net-(IC21-1FSEN)") (class "Default")
      (node (ref "IC21") (pin "20") (pinfunction "3FSEN_20") (pintype "input"))
      (node (ref "IC21") (pin "22") (pinfunction "4FSEN_22") (pintype "input"))
      (node (ref "IC21") (pin "39") (pinfunction "1FSEN_39") (pintype "input"))
      (node (ref "IC21") (pin "41") (pinfunction "2FSEN_41") (pintype "input"))
      (node (ref "R130") (pin "1") (pinfunction "1_1") (pintype "passive"))
      (node (ref "R138") (pin "1") (pinfunction "1_1") (pintype "passive"))
    )
    (net (code "45") (name "Net-(IC24-1FSEN)") (class "Default")
      (node (ref "IC24") (pin "20") (pinfunction "3FSEN_20") (pintype "input"))
      (node (ref "IC24") (pin "22") (pinfunction "4FSEN_22") (pintype "input"))
      (node (ref "IC24") (pin "39") (pinfunction "1FSEN_39") (pintype "input"))
      (node (ref "IC24") (pin "41") (pinfunction "2FSEN_41") (pintype "input"))
      (node (ref "R134") (pin "1") (pinfunction "1_1") (pintype "passive"))
      (node (ref "R140") (pin "1") (pinfunction "1_1") (pintype "passive"))
    )
    (net (code "46") (name "Net-(IC30-FB)") (class "Default")
      (node (ref "IC30") (pin "5") (pinfunction "FB_5") (pintype "input"))
      (node (ref "R167") (pin "1") (pinfunction "1_1") (pintype "passive"))
      (node (ref "R173") (pin "2") (pinfunction "2_2") (pintype "passive"))
    )
    (net (code "47") (name "Net-(IC30-SW)") (class "Default")
      (node (ref "IC30") (pin "9") (pinfunction "SW_9") (pintype "output"))
      (node (ref "L1") (pin "1") (pinfunction "1_1") (pintype "passive"))
    )
    (net (code "48") (name "Net-(LD6A-C)") (class "Default")
      (node (ref "LD6") (pin "1") (pinfunction "C_1") (pintype "passive"))
      (node (ref "R89") (pin "1") (pinfunction "1_1") (pintype "passive"))
    )
    (net (code "49") (name "Net-(LD6B-C)") (class "Default")
      (node (ref "LD6") (pin "3") (pinfunction "C_3") (pintype "passive"))
      (node (ref "R91") (pin "1") (pinfunction "1_1") (pintype "passive"))
    )
    (net (code "50") (name "Net-(LD6C-C)") (class "Default")
      (node (ref "LD6") (pin "5") (pinfunction "C_5") (pintype "passive"))
      (node (ref "R93") (pin "1") (pinfunction "1_1") (pintype "passive"))
    )
    (net (code "51") (name "Net-(LD6D-C)") (class "Default")
      (node (ref "LD6") (pin "7") (pinfunction "C_7") (pintype "passive"))
      (node (ref "R95") (pin "1") (pinfunction "1_1") (pintype "passive"))
    )
    (net (code "52") (name "Net-(LD7A-C)") (class "Default")
      (node (ref "LD7") (pin "1") (pinfunction "C_1") (pintype "passive"))
      (node (ref "R126") (pin "1") (pinfunction "1_1") (pintype "passive"))
    )
    (net (code "53") (name "Net-(LD7B-C)") (class "Default")
      (node (ref "LD7") (pin "3") (pinfunction "C_3") (pintype "passive"))
      (node (ref "R128") (pin "1") (pinfunction "1_1") (pintype "passive"))
    )
    (net (code "54") (name "Net-(LD7C-C)") (class "Default")
      (node (ref "LD7") (pin "5") (pinfunction "C_5") (pintype "passive"))
      (node (ref "R131") (pin "1") (pinfunction "1_1") (pintype "passive"))
    )
    (net (code "55") (name "Net-(LD7D-C)") (class "Default")
      (node (ref "LD7") (pin "7") (pinfunction "C_7") (pintype "passive"))
      (node (ref "R132") (pin "1") (pinfunction "1_1") (pintype "passive"))
    )
    (net (code "56") (name "P3V3") (class "Default")
      (node (ref "C100") (pin "2") (pinfunction "2_2") (pintype "passive"))
      (node (ref "C101") (pin "2") (pinfunction "2_2") (pintype "passive"))
      (node (ref "C102") (pin "2") (pinfunction "2_2") (pintype "passive"))
      (node (ref "C103") (pin "2") (pinfunction "2_2") (pintype "passive"))
      (node (ref "C104") (pin "2") (pinfunction "2_2") (pintype "passive"))
      (node (ref "C105") (pin "2") (pinfunction "2_2") (pintype "passive"))
      (node (ref "C106") (pin "2") (pinfunction "2_2") (pintype "passive"))
      (node (ref "C107") (pin "2") (pinfunction "2_2") (pintype "passive"))
      (node (ref "C108") (pin "2") (pinfunction "2_2") (pintype "passive"))
      (node (ref "C109") (pin "2") (pinfunction "2_2") (pintype "passive"))
      (node (ref "C110") (pin "1") (pinfunction "1_1") (pintype "passive"))
      (node (ref "C15") (pin "2") (pinfunction "2_2") (pintype "passive"))
      (node (ref "C16") (pin "2") (pinfunction "2_2") (pintype "passive"))
      (node (ref "C17") (pin "2") (pinfunction "2_2") (pintype "passive"))
      (node (ref "C18") (pin "1") (pinfunction "1_1") (pintype "passive"))
      (node (ref "C72") (pin "2") (pinfunction "2_2") (pintype "passive"))
      (node (ref "C73") (pin "2") (pinfunction "2_2") (pintype "passive"))
      (node (ref "C97") (pin "2") (pinfunction "2_2") (pintype "passive"))
      (node (ref "C98") (pin "2") (pinfunction "2_2") (pintype "passive"))
      (node (ref "C99") (pin "2") (pinfunction "2_2") (pintype "passive"))
      (node (ref "D2") (pin "5") (pinfunction "VBUS_5") (pintype "power_in"))
      (node (ref "D4") (pin "5") (pinfunction "VBUS_5") (pintype "power_in"))
      (node (ref "D6") (pin "5") (pinfunction "VBUS_5") (pintype "power_in"))
      (node (ref "D7") (pin "5") (pinfunction "VBUS_5") (pintype "power_in"))
      (node (ref "IC21") (pin "11") (pinfunction "VCC_11") (pintype "power_in"))
      (node (ref "IC21") (pin "15") (pinfunction "VCC_15") (pintype "power_in"))
      (node (ref "IC21") (pin "16") (pinfunction "VCC_16") (pintype "power_in"))
      (node (ref "IC21") (pin "2") (pinfunction "VCC_2") (pintype "power_in"))
      (node (ref "IC21") (pin "24") (pinfunction "VCC_24") (pintype "power_in"))
      (node (ref "IC21") (pin "30") (pinfunction "PDN_30") (pintype "input"))
      (node (ref "IC21") (pin "37") (pinfunction "VCC_37") (pintype "power_in"))
      (node (ref "IC21") (pin "45") (pinfunction "VCC_45") (pintype "power_in"))
      (node (ref "IC21") (pin "46") (pinfunction "VCC_46") (pintype "power_in"))
      (node (ref "IC24") (pin "11") (pinfunction "VCC_11") (pintype "power_in"))
      (node (ref "IC24") (pin "15") (pinfunction "VCC_15") (pintype "power_in"))
      (node (ref "IC24") (pin "16") (pinfunction "VCC_16") (pintype "power_in"))
      (node (ref "IC24") (pin "2") (pinfunction "VCC_2") (pintype "power_in"))
      (node (ref "IC24") (pin "24") (pinfunction "VCC_24") (pintype "power_in"))
      (node (ref "IC24") (pin "30") (pinfunction "PDN_30") (pintype "input"))
      (node (ref "IC24") (pin "37") (pinfunction "VCC_37") (pintype "power_in"))
      (node (ref "IC24") (pin "45") (pinfunction "VCC_45") (pintype "power_in"))
      (node (ref "IC24") (pin "46") (pinfunction "VCC_46") (pintype "power_in"))
      (node (ref "IC30") (pin "10") (pinfunction "VOS_10") (pintype "input"))
      (node (ref "IC30") (pin "8") (pinfunction "SLEEP_8") (pintype "input"))
      (node (ref "J12") (pin "6") (pinfunction "6_6") (pintype "bidirectional"))
      (node (ref "J12") (pin "7") (pinfunction "7_7") (pintype "bidirectional"))
      (node (ref "L1") (pin "2") (pinfunction "2_2") (pintype "passive"))
      (node (ref "LD6") (pin "2") (pinfunction "A_2") (pintype "passive"))
      (node (ref "LD6") (pin "4") (pinfunction "A_4") (pintype "passive"))
      (node (ref "LD6") (pin "6") (pinfunction "A_6") (pintype "passive"))
      (node (ref "LD6") (pin "8") (pinfunction "A_8") (pintype "passive"))
      (node (ref "LD7") (pin "2") (pinfunction "A_2") (pintype "passive"))
      (node (ref "LD7") (pin "4") (pinfunction "A_4") (pintype "passive"))
      (node (ref "LD7") (pin "6") (pinfunction "A_6") (pintype "passive"))
      (node (ref "LD7") (pin "8") (pinfunction "A_8") (pintype "passive"))
      (node (ref "R100") (pin "2") (pinfunction "2_2") (pintype "passive"))
      (node (ref "R102") (pin "2") (pinfunction "2_2") (pintype "passive"))
      (node (ref "R104") (pin "2") (pinfunction "2_2") (pintype "passive"))
      (node (ref "R133") (pin "1") (pinfunction "1_1") (pintype "passive"))
      (node (ref "R152") (pin "1") (pinfunction "1_1") (pintype "passive"))
      (node (ref "R167") (pin "2") (pinfunction "2_2") (pintype "passive"))
      (node (ref "R90") (pin "2") (pinfunction "2_2") (pintype "passive"))
      (node (ref "R92") (pin "2") (pinfunction "2_2") (pintype "passive"))
      (node (ref "R94") (pin "2") (pinfunction "2_2") (pintype "passive"))
      (node (ref "R96") (pin "2") (pinfunction "2_2") (pintype "passive"))
      (node (ref "R98") (pin "2") (pinfunction "2_2") (pintype "passive"))
      (node (ref "SW1") (pin "1") (pinfunction "1_1") (pintype "bidirectional"))
      (node (ref "W1") (pin "1") (pinfunction "1_1") (pintype "bidirectional"))
    )
    (net (code "57") (name "P3V3_MP") (class "Default")
      (node (ref "J11") (pin "30") (pinfunction "30_30") (pintype "bidirectional"))
      (node (ref "W1") (pin "2") (pinfunction "2_2") (pintype "bidirectional"))
    )
    (net (code "58") (name "P12V0") (class "Default")
      (node (ref "C74") (pin "2") (pinfunction "2_2") (pintype "passive"))
      (node (ref "C75") (pin "2") (pinfunction "2_2") (pintype "passive"))
      (node (ref "IC30") (pin "2") (pinfunction "VIN_2") (pintype "input"))
      (node (ref "IC30") (pin "3") (pinfunction "EN_3") (pintype "input"))
      (node (ref "J11") (pin "28") (pinfunction "28_28") (pintype "bidirectional"))
      (node (ref "J11") (pin "29") (pinfunction "29_29") (pintype "bidirectional"))
      (node (ref "J50") (pin "1") (pinfunction "1_1") (pintype "bidirectional"))
    )
    (net (code "59") (name "unconnected-(IC21-NC-Pad17)") (class "Default")
      (node (ref "IC21") (pin "17") (pinfunction "NC_17") (pintype "passive"))
    )
    (net (code "60") (name "unconnected-(IC21-NC-Pad44)") (class "Default")
      (node (ref "IC21") (pin "44") (pinfunction "NC_44") (pintype "passive"))
    )
    (net (code "61") (name "unconnected-(IC24-NC-Pad17)") (class "Default")
      (node (ref "IC24") (pin "17") (pinfunction "NC_17") (pintype "passive"))
    )
    (net (code "62") (name "unconnected-(IC24-NC-Pad44)") (class "Default")
      (node (ref "IC24") (pin "44") (pinfunction "NC_44") (pintype "passive"))
    )
    (net (code "63") (name "unconnected-(IC30-NC-Pad4)") (class "Default")
      (node (ref "IC30") (pin "4") (pinfunction "NC_4") (pintype "passive"))
    )
    (net (code "64") (name "unconnected-(IC30-PG-Pad7)") (class "Default")
      (node (ref "IC30") (pin "7") (pinfunction "PG_7") (pintype "output"))
    )
    (net (code "65") (name "unconnected-(J50-Pad3)") (class "Default")
      (node (ref "J50") (pin "3") (pinfunction "3_3") (pintype "bidirectional"))
    )
  )
)
